# ProPrj_Maggy_4_1_2025-02-07.net
KiCad netlist of a schematic drawn in EasyEDA Pro
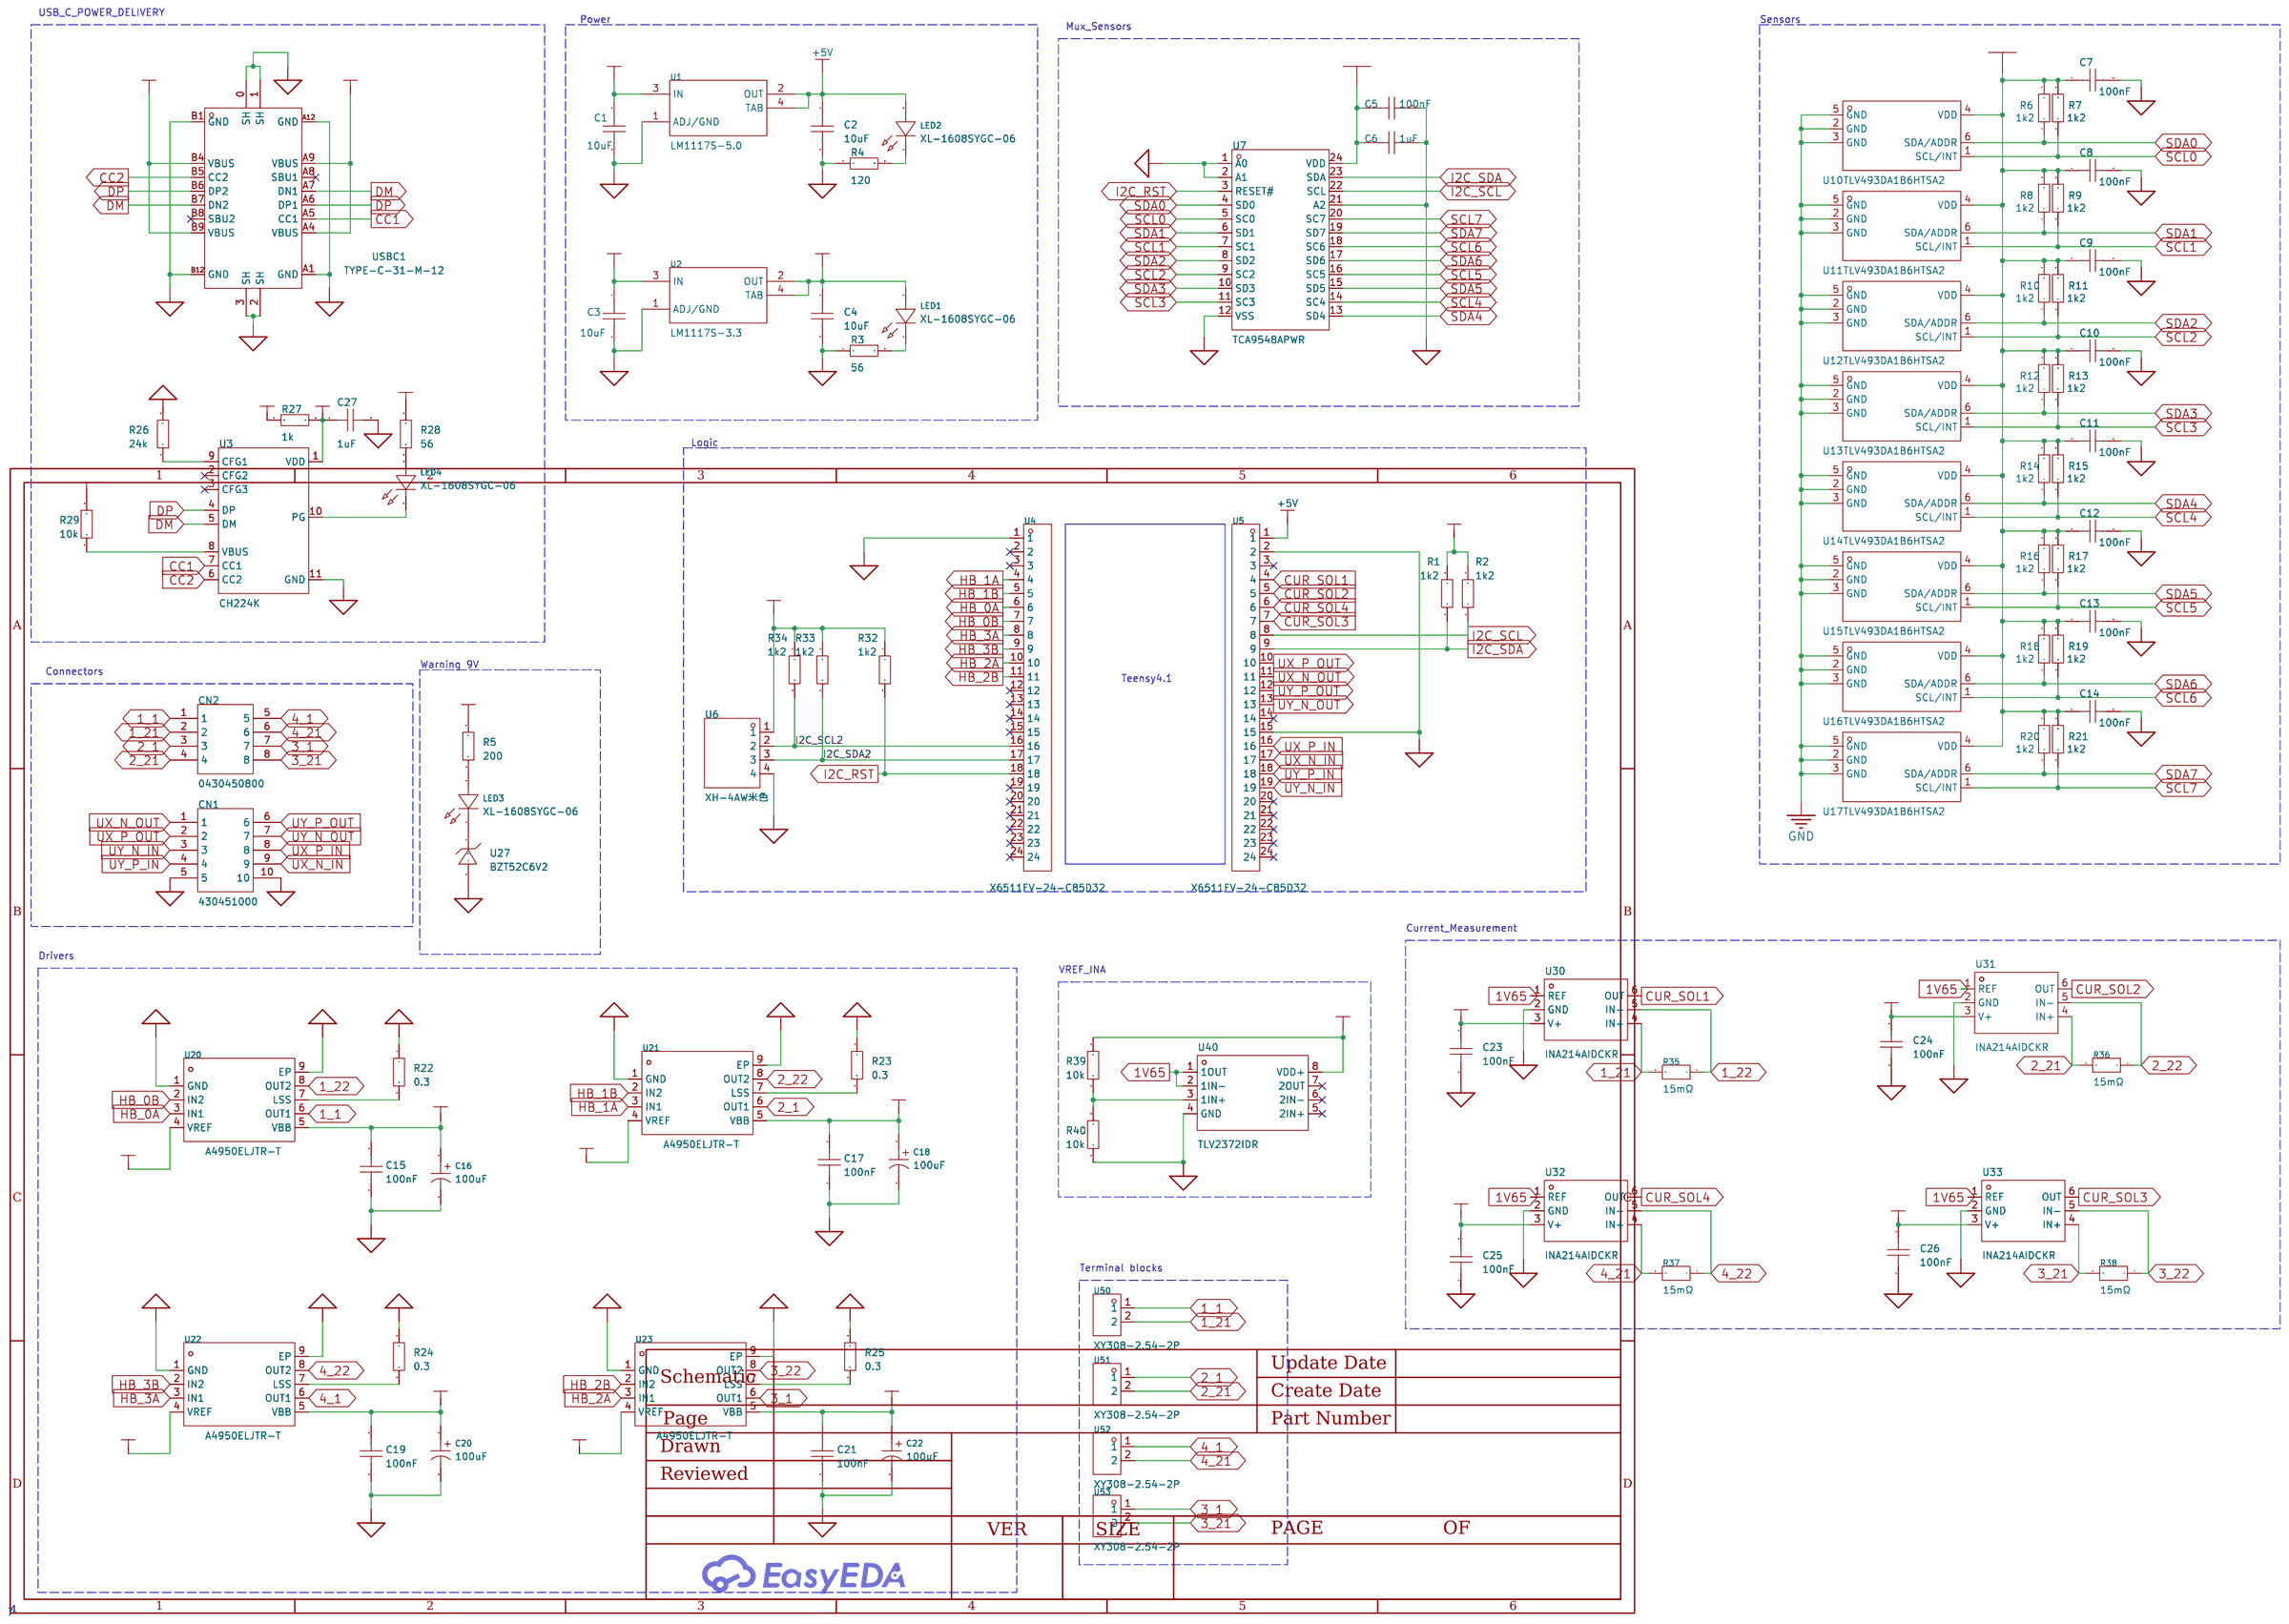
[diagram p0: schematic sheet]

(export (version "E")
  (design (tool "Eeschema 10.0.6"))
  (components
    (comp (ref "C1")
      (value "10uF")
      (footprint "easyedapro:C0805")
      (libsource (lib "easyedapro") (part "CAP"))
    )
    (comp (ref "C2")
      (value "10uF")
      (footprint "easyedapro:C0805")
      (libsource (lib "easyedapro") (part "CAP"))
    )
    (comp (ref "C3")
      (value "10uF")
      (footprint "easyedapro:C0805")
      (libsource (lib "easyedapro") (part "CAP"))
    )
    (comp (ref "C4")
      (value "10uF")
      (footprint "easyedapro:C0805")
      (libsource (lib "easyedapro") (part "CAP"))
    )
    (comp (ref "C5")
      (value "100nF")
      (footprint "easyedapro:C0805")
      (libsource (lib "easyedapro") (part "CAP"))
    )
    (comp (ref "C6") (value "1uF") (footprint "easyedapro:C0805") (libsource (lib "easyedapro") (part "CAP")))
    (comp (ref "C7")
      (value "100nF")
      (footprint "easyedapro:C0805")
      (libsource (lib "easyedapro") (part "CAP"))
    )
    (comp (ref "C8")
      (value "100nF")
      (footprint "easyedapro:C0805")
      (libsource (lib "easyedapro") (part "CAP"))
    )
    (comp (ref "C9")
      (value "100nF")
      (footprint "easyedapro:C0805")
      (libsource (lib "easyedapro") (part "CAP"))
    )
    (comp (ref "C10")
      (value "100nF")
      (footprint "easyedapro:C0805")
      (libsource (lib "easyedapro") (part "CAP"))
    )
    (comp (ref "C11")
      (value "100nF")
      (footprint "easyedapro:C0805")
      (libsource (lib "easyedapro") (part "CAP"))
    )
    (comp (ref "C12")
      (value "100nF")
      (footprint "easyedapro:C0805")
      (libsource (lib "easyedapro") (part "CAP"))
    )
    (comp (ref "C13")
      (value "100nF")
      (footprint "easyedapro:C0805")
      (libsource (lib "easyedapro") (part "CAP"))
    )
    (comp (ref "C14")
      (value "100nF")
      (footprint "easyedapro:C0805")
      (libsource (lib "easyedapro") (part "CAP"))
    )
    (comp (ref "C15")
      (value "100nF")
      (footprint "easyedapro:C0805")
      (libsource (lib "easyedapro") (part "CAP"))
    )
    (comp (ref "C16")
      (value "100uF")
      (footprint "easyedapro:CAP-SMD_BD6.3-L6.6-W6.6-LS7.2-FD")
      (fields (field (name "Manufacturer Part") "RST100UF35V009") (field (name "Manufacturer") "KNSCHA(科尼盛)"))
      (libsource (lib "easyedapro") (part "RST100UF35V009"))
    )
    (comp (ref "C17")
      (value "100nF")
      (footprint "easyedapro:C0805")
      (libsource (lib "easyedapro") (part "CAP"))
    )
    (comp (ref "C18")
      (value "100uF")
      (footprint "easyedapro:CAP-SMD_BD6.3-L6.6-W6.6-LS7.2-FD")
      (fields (field (name "Manufacturer Part") "RST100UF35V009") (field (name "Manufacturer") "KNSCHA(科尼盛)"))
      (libsource (lib "easyedapro") (part "RST100UF35V009"))
    )
    (comp (ref "C19")
      (value "100nF")
      (footprint "easyedapro:C0805")
      (libsource (lib "easyedapro") (part "CAP"))
    )
    (comp (ref "C20")
      (value "100uF")
      (footprint "easyedapro:CAP-SMD_BD6.3-L6.6-W6.6-LS7.2-FD")
      (fields (field (name "Manufacturer Part") "RST100UF35V009") (field (name "Manufacturer") "KNSCHA(科尼盛)"))
      (libsource (lib "easyedapro") (part "RST100UF35V009"))
    )
    (comp (ref "C21")
      (value "100nF")
      (footprint "easyedapro:C0805")
      (libsource (lib "easyedapro") (part "CAP"))
    )
    (comp (ref "C22")
      (value "100uF")
      (footprint "easyedapro:CAP-SMD_BD6.3-L6.6-W6.6-LS7.2-FD")
      (fields (field (name "Manufacturer Part") "RST100UF35V009") (field (name "Manufacturer") "KNSCHA(科尼盛)"))
      (libsource (lib "easyedapro") (part "RST100UF35V009"))
    )
    (comp (ref "C23")
      (value "100nF")
      (footprint "easyedapro:C0805")
      (libsource (lib "easyedapro") (part "CAP"))
    )
    (comp (ref "C24")
      (value "100nF")
      (footprint "easyedapro:C0805")
      (libsource (lib "easyedapro") (part "CAP"))
    )
    (comp (ref "C25")
      (value "100nF")
      (footprint "easyedapro:C0805")
      (libsource (lib "easyedapro") (part "CAP"))
    )
    (comp (ref "C26")
      (value "100nF")
      (footprint "easyedapro:C0805")
      (libsource (lib "easyedapro") (part "CAP"))
    )
    (comp (ref "C27")
      (value "1uF")
      (footprint "easyedapro:C0805")
      (libsource (lib "easyedapro") (part "CAP"))
    )
    (comp (ref "CN1")
      (value "430451000")
      (footprint "easyedapro:CONN-TH_43045-1000")
      (fields (field (name "Manufacturer") "MOLEX"))
      (libsource (lib "easyedapro") (part "0430451000"))
    )
    (comp (ref "CN2")
      (value "0430450800")
      (footprint "easyedapro:CONN-TH_0430450800")
      (fields (field (name "Manufacturer") "MOLEX"))
      (libsource (lib "easyedapro") (part "0430450800"))
    )
    (comp (ref "LED1")
      (value "XL-1608SYGC-06")
      (footprint "easyedapro:LED0603-RD_GREEN")
      (fields (field (name "Manufacturer") "XINGLIGHT(成兴光)"))
      (libsource (lib "easyedapro") (part "XL-1608SYGC-06"))
    )
    (comp (ref "LED2")
      (value "XL-1608SYGC-06")
      (footprint "easyedapro:LED0603-RD_RED")
      (fields (field (name "Manufacturer") "XINGLIGHT(成兴光)"))
      (libsource (lib "easyedapro") (part "XL-1608SURC-06"))
    )
    (comp (ref "LED3")
      (value "XL-1608SYGC-06")
      (footprint "easyedapro:LED0603-RD_GREEN")
      (fields (field (name "Manufacturer") "XINGLIGHT(成兴光)"))
      (libsource (lib "easyedapro") (part "XL-1608SYGC-06"))
    )
    (comp (ref "LED4")
      (value "XL-1608SYGC-06")
      (footprint "easyedapro:LED0603-RD_GREEN")
      (fields (field (name "Manufacturer") "XINGLIGHT(成兴光)"))
      (libsource (lib "easyedapro") (part "XL-1608SYGC-06"))
    )
    (comp (ref "R1") (value "1k2") (footprint "easyedapro:R0805") (libsource (lib "easyedapro") (part "Res")))
    (comp (ref "R2") (value "1k2") (footprint "easyedapro:R0805") (libsource (lib "easyedapro") (part "Res")))
    (comp (ref "R3") (value "56") (footprint "easyedapro:R0805") (libsource (lib "easyedapro") (part "Res")))
    (comp (ref "R4") (value "120") (footprint "easyedapro:R0805") (libsource (lib "easyedapro") (part "Res")))
    (comp (ref "R5") (value "200") (footprint "easyedapro:R0805") (libsource (lib "easyedapro") (part "Res")))
    (comp (ref "R6") (value "1k2") (libsource (lib "easyedapro") (part "Res")))
    (comp (ref "R7") (value "1k2") (libsource (lib "easyedapro") (part "Res")))
    (comp (ref "R8") (value "1k2") (libsource (lib "easyedapro") (part "Res")))
    (comp (ref "R9") (value "1k2") (libsource (lib "easyedapro") (part "Res")))
    (comp (ref "R10") (value "1k2") (libsource (lib "easyedapro") (part "Res")))
    (comp (ref "R11") (value "1k2") (libsource (lib "easyedapro") (part "Res")))
    (comp (ref "R12") (value "1k2") (libsource (lib "easyedapro") (part "Res")))
    (comp (ref "R13") (value "1k2") (libsource (lib "easyedapro") (part "Res")))
    (comp (ref "R14") (value "1k2") (libsource (lib "easyedapro") (part "Res")))
    (comp (ref "R15") (value "1k2") (libsource (lib "easyedapro") (part "Res")))
    (comp (ref "R16") (value "1k2") (libsource (lib "easyedapro") (part "Res")))
    (comp (ref "R17") (value "1k2") (libsource (lib "easyedapro") (part "Res")))
    (comp (ref "R18") (value "1k2") (libsource (lib "easyedapro") (part "Res")))
    (comp (ref "R19") (value "1k2") (libsource (lib "easyedapro") (part "Res")))
    (comp (ref "R20") (value "1k2") (libsource (lib "easyedapro") (part "Res")))
    (comp (ref "R21") (value "1k2") (libsource (lib "easyedapro") (part "Res")))
    (comp (ref "R22")
      (value "0.3")
      (footprint "easyedapro:R0805")
      (libsource (lib "easyedapro") (part "Res"))
    )
    (comp (ref "R23")
      (value "0.3")
      (footprint "easyedapro:R0805")
      (libsource (lib "easyedapro") (part "Res"))
    )
    (comp (ref "R24")
      (value "0.3")
      (footprint "easyedapro:R0805")
      (libsource (lib "easyedapro") (part "Res"))
    )
    (comp (ref "R25")
      (value "0.3")
      (footprint "easyedapro:R0805")
      (libsource (lib "easyedapro") (part "Res"))
    )
    (comp (ref "R26") (value "24k") (libsource (lib "easyedapro") (part "Res")))
    (comp (ref "R27") (value "1k") (libsource (lib "easyedapro") (part "Res")))
    (comp (ref "R28") (value "56") (footprint "easyedapro:R0805") (libsource (lib "easyedapro") (part "Res")))
    (comp (ref "R29") (value "10k") (libsource (lib "easyedapro") (part "Res")))
    (comp (ref "R32")
      (value "1k2")
      (footprint "easyedapro:R0805")
      (libsource (lib "easyedapro") (part "Res"))
    )
    (comp (ref "R33")
      (value "1k2")
      (footprint "easyedapro:R0805")
      (libsource (lib "easyedapro") (part "Res"))
    )
    (comp (ref "R34")
      (value "1k2")
      (footprint "easyedapro:R0805")
      (libsource (lib "easyedapro") (part "Res"))
    )
    (comp (ref "R35")
      (value "15mΩ")
      (footprint "easyedapro:R1206")
      (fields
        (field (name "Manufacturer Part") "1206W3F100MT5E")
        (field (name "Manufacturer") "UNI-ROYAL(厚声)")
      )
      (libsource (lib "easyedapro") (part "1206W3F100MT5E"))
    )
    (comp (ref "R36")
      (value "15mΩ")
      (footprint "easyedapro:R1206")
      (fields
        (field (name "Manufacturer Part") "1206W3F100MT5E")
        (field (name "Manufacturer") "UNI-ROYAL(厚声)")
      )
      (libsource (lib "easyedapro") (part "1206W3F100MT5E"))
    )
    (comp (ref "R37")
      (value "15mΩ")
      (footprint "easyedapro:R1206")
      (fields
        (field (name "Manufacturer Part") "1206W3F100MT5E")
        (field (name "Manufacturer") "UNI-ROYAL(厚声)")
      )
      (libsource (lib "easyedapro") (part "1206W3F100MT5E"))
    )
    (comp (ref "R38")
      (value "15mΩ")
      (footprint "easyedapro:R1206")
      (fields
        (field (name "Manufacturer Part") "1206W3F100MT5E")
        (field (name "Manufacturer") "UNI-ROYAL(厚声)")
      )
      (libsource (lib "easyedapro") (part "1206W3F100MT5E"))
    )
    (comp (ref "R39") (value "10k") (libsource (lib "easyedapro") (part "Res")))
    (comp (ref "R40") (value "10k") (libsource (lib "easyedapro") (part "Res")))
    (comp (ref "U1")
      (value "LM1117S-5.0")
      (footprint "easyedapro:SOT-223-3_L6.5-W3.4-P2.30-LS7.0-BR")
      (fields (field (name "Manufacturer") "HTC"))
      (libsource (lib "easyedapro") (part "LM1117S-5.0"))
    )
    (comp (ref "U2")
      (value "LM1117S-3.3")
      (footprint "easyedapro:SOT-223-3_L6.5-W3.4-P2.30-LS7.0-BR")
      (fields (field (name "Manufacturer") "HTC"))
      (libsource (lib "easyedapro") (part "LM1117S-3.3"))
    )
    (comp (ref "U3")
      (value "CH224K")
      (footprint "easyedapro:ESSOP-10_L4.9-W3.9-P1.0-LS6.0-TL-EP")
      (description "Applications Function:USB充电芯片")
      (fields (field (name "Manufacturer") "WCH(南京沁恒)"))
      (libsource (lib "easyedapro") (part "CH224K"))
    )
    (comp (ref "U4")
      (value "X6511FV-24-C85D32")
      (footprint "easyedapro:HDR-TH_24P-P2.54-V-F")
      (fields (field (name "Manufacturer") "XKB Connectivity(中国星坤)"))
      (libsource (lib "easyedapro") (part "X6511FV-24-C85D32"))
    )
    (comp (ref "U5")
      (value "X6511FV-24-C85D32")
      (footprint "easyedapro:HDR-TH_24P-P2.54-V-F")
      (fields (field (name "Manufacturer") "XKB Connectivity(中国星坤)"))
      (libsource (lib "easyedapro") (part "X6511FV-24-C85D32"))
    )
    (comp (ref "U6")
      (value "XH-4AW米色")
      (fields (field (name "Manufacturer") "BOOMELE(博穆精密)"))
      (libsource (lib "easyedapro") (part "S4B-PH-KL(LF)(SN)"))
    )
    (comp (ref "U7")
      (value "TCA9548APWR")
      (fields (field (name "Manufacturer") "TI(德州仪器)"))
      (libsource (lib "easyedapro") (part "PCA9548APW"))
    )
    (comp (ref "U10")
      (value "TLV493DA1B6HTSA2")
      (fields (field (name "Manufacturer") "Infineon(英飞凌)"))
      (libsource (lib "easyedapro") (part "TLV493DA1B6HTSA2"))
    )
    (comp (ref "U11")
      (value "TLV493DA1B6HTSA2")
      (fields (field (name "Manufacturer") "Infineon(英飞凌)"))
      (libsource (lib "easyedapro") (part "TLV493DA1B6HTSA2"))
    )
    (comp (ref "U12")
      (value "TLV493DA1B6HTSA2")
      (fields (field (name "Manufacturer") "Infineon(英飞凌)"))
      (libsource (lib "easyedapro") (part "TLV493DA1B6HTSA2"))
    )
    (comp (ref "U13")
      (value "TLV493DA1B6HTSA2")
      (fields (field (name "Manufacturer") "Infineon(英飞凌)"))
      (libsource (lib "easyedapro") (part "TLV493DA1B6HTSA2"))
    )
    (comp (ref "U14")
      (value "TLV493DA1B6HTSA2")
      (fields (field (name "Manufacturer") "Infineon(英飞凌)"))
      (libsource (lib "easyedapro") (part "TLV493DA1B6HTSA2"))
    )
    (comp (ref "U15")
      (value "TLV493DA1B6HTSA2")
      (fields (field (name "Manufacturer") "Infineon(英飞凌)"))
      (libsource (lib "easyedapro") (part "TLV493DA1B6HTSA2"))
    )
    (comp (ref "U16")
      (value "TLV493DA1B6HTSA2")
      (fields (field (name "Manufacturer") "Infineon(英飞凌)"))
      (libsource (lib "easyedapro") (part "TLV493DA1B6HTSA2"))
    )
    (comp (ref "U17")
      (value "TLV493DA1B6HTSA2")
      (fields (field (name "Manufacturer") "Infineon(英飞凌)"))
      (libsource (lib "easyedapro") (part "TLV493DA1B6HTSA2"))
    )
    (comp (ref "U20")
      (value "A4950ELJTR-T")
      (footprint "easyedapro:SOIC-8_L4.9-W3.9-P1.27-LS6.0-BL-EP")
      (fields (field (name "Manufacturer") "ALLEGRO(美国埃戈罗)"))
      (libsource (lib "easyedapro") (part "A4950ELJTR-T"))
    )
    (comp (ref "U21")
      (value "A4950ELJTR-T")
      (footprint "easyedapro:SOIC-8_L4.9-W3.9-P1.27-LS6.0-BL-EP")
      (fields (field (name "Manufacturer") "ALLEGRO(美国埃戈罗)"))
      (libsource (lib "easyedapro") (part "A4950ELJTR-T"))
    )
    (comp (ref "U22")
      (value "A4950ELJTR-T")
      (footprint "easyedapro:SOIC-8_L4.9-W3.9-P1.27-LS6.0-BL-EP")
      (fields (field (name "Manufacturer") "ALLEGRO(美国埃戈罗)"))
      (libsource (lib "easyedapro") (part "A4950ELJTR-T"))
    )
    (comp (ref "U23")
      (value "A4950ELJTR-T")
      (footprint "easyedapro:SOIC-8_L4.9-W3.9-P1.27-LS6.0-BL-EP")
      (fields (field (name "Manufacturer") "ALLEGRO(美国埃戈罗)"))
      (libsource (lib "easyedapro") (part "A4950ELJTR-T"))
    )
    (comp (ref "U27")
      (value "BZT52C6V2")
      (footprint "easyedapro:SOD-123_L2.7-W1.6-LS3.7-RD")
      (fields (field (name "Manufacturer") "CJ(江苏长电/长晶)"))
      (libsource (lib "easyedapro") (part "BZT52C6V2_C2910064"))
    )
    (comp (ref "U30")
      (value "INA214AIDCKR")
      (footprint "easyedapro:TSSOP-6_L2.0-W1.3-P0.65-LS2.0-BR")
      (fields (field (name "Manufacturer") "TI(德州仪器)"))
      (libsource (lib "easyedapro") (part "INA213AIDCKR"))
    )
    (comp (ref "U31")
      (value "INA214AIDCKR")
      (footprint "easyedapro:TSSOP-6_L2.0-W1.3-P0.65-LS2.0-BR")
      (fields (field (name "Manufacturer") "TI(德州仪器)"))
      (libsource (lib "easyedapro") (part "INA213AIDCKR"))
    )
    (comp (ref "U32")
      (value "INA214AIDCKR")
      (footprint "easyedapro:TSSOP-6_L2.0-W1.3-P0.65-LS2.0-BR")
      (fields (field (name "Manufacturer") "TI(德州仪器)"))
      (libsource (lib "easyedapro") (part "INA213AIDCKR"))
    )
    (comp (ref "U33")
      (value "INA214AIDCKR")
      (footprint "easyedapro:TSSOP-6_L2.0-W1.3-P0.65-LS2.0-BR")
      (fields (field (name "Manufacturer") "TI(德州仪器)"))
      (libsource (lib "easyedapro") (part "INA213AIDCKR"))
    )
    (comp (ref "U40")
      (value "TLV2372IDR")
      (footprint "easyedapro:SOIC-8_L4.9-W3.9-P1.27-LS6.0-BL")
      (fields (field (name "Manufacturer") "TI(德州仪器)"))
      (libsource (lib "easyedapro") (part "TLV2372IDR"))
    )
    (comp (ref "U50")
      (value "XY308-2.54-2P")
      (footprint "easyedapro:CONN-TH_XY308-2.54-2P")
      (fields (field (name "Manufacturer") "XINLAIYA(新莱亚)"))
      (libsource (lib "easyedapro") (part "XY308-2.54-2P"))
    )
    (comp (ref "U51")
      (value "XY308-2.54-2P")
      (footprint "easyedapro:CONN-TH_XY308-2.54-2P")
      (fields (field (name "Manufacturer") "XINLAIYA(新莱亚)"))
      (libsource (lib "easyedapro") (part "XY308-2.54-2P"))
    )
    (comp (ref "U52")
      (value "XY308-2.54-2P")
      (footprint "easyedapro:CONN-TH_XY308-2.54-2P")
      (fields (field (name "Manufacturer") "XINLAIYA(新莱亚)"))
      (libsource (lib "easyedapro") (part "XY308-2.54-2P"))
    )
    (comp (ref "U53")
      (value "XY308-2.54-2P")
      (footprint "easyedapro:CONN-TH_XY308-2.54-2P")
      (fields (field (name "Manufacturer") "XINLAIYA(新莱亚)"))
      (libsource (lib "easyedapro") (part "XY308-2.54-2P"))
    )
    (comp (ref "USBC1")
      (value "TYPE-C-31-M-12")
      (footprint "easyedapro:USB-C_SMD-TYPE-C-31-M-12")
      (fields (field (name "Manufacturer") "韩国韩荣"))
      (libsource (lib "easyedapro") (part "TYPE-C-31-M-12"))
    )
  )
  (nets
    (net (code "1") (name "+5V") (class "Default")
      (node (ref "C2") (pin "1") (pinfunction "1_1") (pintype "input"))
      (node (ref "LED2") (pin "2") (pinfunction "A_2") (pintype "unspecified"))
      (node (ref "U1") (pin "2") (pinfunction "OUT_2") (pintype "input"))
      (node (ref "U1") (pin "4") (pinfunction "TAB_4") (pintype "input"))
      (node (ref "U5") (pin "1") (pinfunction "1_1") (pintype "input"))
    )
    (net (code "2") (name "/I2C_SCL2") (class "Default")
      (node (ref "R34") (pin "2") (pinfunction "2_2") (pintype "input"))
      (node (ref "U4") (pin "16") (pinfunction "16_16") (pintype "input"))
      (node (ref "U6") (pin "2") (pinfunction "2_2") (pintype "unspecified"))
    )
    (net (code "3") (name "/I2C_SDA2") (class "Default")
      (node (ref "R33") (pin "2") (pinfunction "2_2") (pintype "input"))
      (node (ref "U4") (pin "17") (pinfunction "17_17") (pintype "input"))
      (node (ref "U6") (pin "3") (pinfunction "3_3") (pintype "unspecified"))
    )
    (net (code "4") (name "1V65") (class "Default")
      (node (ref "U30") (pin "1") (pinfunction "REF_1") (pintype "unspecified"))
      (node (ref "U31") (pin "1") (pinfunction "REF_1") (pintype "unspecified"))
      (node (ref "U32") (pin "1") (pinfunction "REF_1") (pintype "unspecified"))
      (node (ref "U33") (pin "1") (pinfunction "REF_1") (pintype "unspecified"))
      (node (ref "U40") (pin "1") (pinfunction "1OUT_1") (pintype "unspecified"))
      (node (ref "U40") (pin "2") (pinfunction "1IN-_2") (pintype "unspecified"))
    )
    (net (code "5") (name "1_1") (class "Default")
      (node (ref "CN2") (pin "1") (pinfunction "1_1") (pintype "unspecified"))
      (node (ref "U20") (pin "6") (pinfunction "OUT1_6") (pintype "unspecified"))
      (node (ref "U50") (pin "1") (pinfunction "1_1") (pintype "unspecified"))
    )
    (net (code "6") (name "1_21") (class "Default")
      (node (ref "CN2") (pin "2") (pinfunction "2_2") (pintype "unspecified"))
      (node (ref "R35") (pin "2") (pinfunction "2_2") (pintype "input"))
      (node (ref "U30") (pin "4") (pinfunction "IN+_4") (pintype "unspecified"))
      (node (ref "U50") (pin "2") (pinfunction "2_2") (pintype "unspecified"))
    )
    (net (code "7") (name "1_22") (class "Default")
      (node (ref "R35") (pin "1") (pinfunction "1_1") (pintype "input"))
      (node (ref "U20") (pin "8") (pinfunction "OUT2_8") (pintype "unspecified"))
      (node (ref "U30") (pin "5") (pinfunction "IN-_5") (pintype "unspecified"))
    )
    (net (code "8") (name "2_1") (class "Default")
      (node (ref "CN2") (pin "3") (pinfunction "3_3") (pintype "unspecified"))
      (node (ref "U21") (pin "6") (pinfunction "OUT1_6") (pintype "unspecified"))
      (node (ref "U51") (pin "1") (pinfunction "1_1") (pintype "unspecified"))
    )
    (net (code "9") (name "2_21") (class "Default")
      (node (ref "CN2") (pin "4") (pinfunction "4_4") (pintype "unspecified"))
      (node (ref "R36") (pin "2") (pinfunction "2_2") (pintype "input"))
      (node (ref "U31") (pin "4") (pinfunction "IN+_4") (pintype "unspecified"))
      (node (ref "U51") (pin "2") (pinfunction "2_2") (pintype "unspecified"))
    )
    (net (code "10") (name "2_22") (class "Default")
      (node (ref "R36") (pin "1") (pinfunction "1_1") (pintype "input"))
      (node (ref "U21") (pin "8") (pinfunction "OUT2_8") (pintype "unspecified"))
      (node (ref "U31") (pin "5") (pinfunction "IN-_5") (pintype "unspecified"))
    )
    (net (code "11") (name "3V3") (class "Default")
      (node (ref "C10") (pin "1") (pinfunction "1_1") (pintype "input"))
      (node (ref "C11") (pin "1") (pinfunction "1_1") (pintype "input"))
      (node (ref "C12") (pin "1") (pinfunction "1_1") (pintype "input"))
      (node (ref "C13") (pin "1") (pinfunction "1_1") (pintype "input"))
      (node (ref "C14") (pin "1") (pinfunction "1_1") (pintype "input"))
      (node (ref "C23") (pin "2") (pinfunction "2_2") (pintype "input"))
      (node (ref "C24") (pin "2") (pinfunction "2_2") (pintype "input"))
      (node (ref "C25") (pin "2") (pinfunction "2_2") (pintype "input"))
      (node (ref "C26") (pin "2") (pinfunction "2_2") (pintype "input"))
      (node (ref "C27") (pin "1") (pinfunction "1_1") (pintype "input"))
      (node (ref "C4") (pin "1") (pinfunction "1_1") (pintype "input"))
      (node (ref "C5") (pin "1") (pinfunction "1_1") (pintype "input"))
      (node (ref "C6") (pin "2") (pinfunction "2_2") (pintype "input"))
      (node (ref "C7") (pin "1") (pinfunction "1_1") (pintype "input"))
      (node (ref "C8") (pin "1") (pinfunction "1_1") (pintype "input"))
      (node (ref "C9") (pin "1") (pinfunction "1_1") (pintype "input"))
      (node (ref "LED1") (pin "2") (pinfunction "A_2") (pintype "input"))
      (node (ref "R1") (pin "2") (pinfunction "2_2") (pintype "input"))
      (node (ref "R10") (pin "2") (pinfunction "2_2") (pintype "input"))
      (node (ref "R11") (pin "2") (pinfunction "2_2") (pintype "input"))
      (node (ref "R12") (pin "2") (pinfunction "2_2") (pintype "input"))
      (node (ref "R13") (pin "2") (pinfunction "2_2") (pintype "input"))
      (node (ref "R14") (pin "2") (pinfunction "2_2") (pintype "input"))
      (node (ref "R15") (pin "2") (pinfunction "2_2") (pintype "input"))
      (node (ref "R16") (pin "2") (pinfunction "2_2") (pintype "input"))
      (node (ref "R17") (pin "2") (pinfunction "2_2") (pintype "input"))
      (node (ref "R18") (pin "2") (pinfunction "2_2") (pintype "input"))
      (node (ref "R19") (pin "2") (pinfunction "2_2") (pintype "input"))
      (node (ref "R2") (pin "2") (pinfunction "2_2") (pintype "input"))
      (node (ref "R20") (pin "2") (pinfunction "2_2") (pintype "input"))
      (node (ref "R21") (pin "2") (pinfunction "2_2") (pintype "input"))
      (node (ref "R27") (pin "1") (pinfunction "1_1") (pintype "input"))
      (node (ref "R28") (pin "2") (pinfunction "2_2") (pintype "input"))
      (node (ref "R32") (pin "1") (pinfunction "1_1") (pintype "input"))
      (node (ref "R33") (pin "1") (pinfunction "1_1") (pintype "input"))
      (node (ref "R34") (pin "1") (pinfunction "1_1") (pintype "input"))
      (node (ref "R39") (pin "2") (pinfunction "2_2") (pintype "input"))
      (node (ref "R6") (pin "2") (pinfunction "2_2") (pintype "input"))
      (node (ref "R7") (pin "2") (pinfunction "2_2") (pintype "input"))
      (node (ref "R8") (pin "2") (pinfunction "2_2") (pintype "input"))
      (node (ref "R9") (pin "2") (pinfunction "2_2") (pintype "input"))
      (node (ref "U10") (pin "4") (pinfunction "VDD_4") (pintype "input"))
      (node (ref "U11") (pin "4") (pinfunction "VDD_4") (pintype "input"))
      (node (ref "U12") (pin "4") (pinfunction "VDD_4") (pintype "input"))
      (node (ref "U13") (pin "4") (pinfunction "VDD_4") (pintype "input"))
      (node (ref "U14") (pin "4") (pinfunction "VDD_4") (pintype "input"))
      (node (ref "U15") (pin "4") (pinfunction "VDD_4") (pintype "input"))
      (node (ref "U16") (pin "4") (pinfunction "VDD_4") (pintype "input"))
      (node (ref "U17") (pin "4") (pinfunction "VDD_4") (pintype "input"))
      (node (ref "U2") (pin "2") (pinfunction "OUT_2") (pintype "input"))
      (node (ref "U2") (pin "4") (pinfunction "TAB_4") (pintype "input"))
      (node (ref "U20") (pin "4") (pinfunction "VREF_4") (pintype "unspecified"))
      (node (ref "U21") (pin "4") (pinfunction "VREF_4") (pintype "unspecified"))
      (node (ref "U22") (pin "4") (pinfunction "VREF_4") (pintype "unspecified"))
      (node (ref "U23") (pin "4") (pinfunction "VREF_4") (pintype "unspecified"))
      (node (ref "U3") (pin "1") (pinfunction "VDD_1") (pintype "unspecified"))
      (node (ref "U30") (pin "3") (pinfunction "V+_3") (pintype "unspecified"))
      (node (ref "U31") (pin "3") (pinfunction "V+_3") (pintype "unspecified"))
      (node (ref "U32") (pin "3") (pinfunction "V+_3") (pintype "unspecified"))
      (node (ref "U33") (pin "3") (pinfunction "V+_3") (pintype "unspecified"))
      (node (ref "U40") (pin "8") (pinfunction "VDD+_8") (pintype "unspecified"))
      (node (ref "U6") (pin "1") (pinfunction "1_1") (pintype "unspecified"))
      (node (ref "U7") (pin "24") (pinfunction "VDD_24") (pintype "unspecified"))
    )
    (net (code "12") (name "3_1") (class "Default")
      (node (ref "CN2") (pin "7") (pinfunction "7_7") (pintype "unspecified"))
      (node (ref "U23") (pin "6") (pinfunction "OUT1_6") (pintype "unspecified"))
      (node (ref "U53") (pin "1") (pinfunction "1_1") (pintype "unspecified"))
    )
    (net (code "13") (name "3_21") (class "Default")
      (node (ref "CN2") (pin "8") (pinfunction "8_8") (pintype "unspecified"))
      (node (ref "R38") (pin "2") (pinfunction "2_2") (pintype "input"))
      (node (ref "U33") (pin "4") (pinfunction "IN+_4") (pintype "unspecified"))
      (node (ref "U53") (pin "2") (pinfunction "2_2") (pintype "unspecified"))
    )
    (net (code "14") (name "3_22") (class "Default")
      (node (ref "R38") (pin "1") (pinfunction "1_1") (pintype "input"))
      (node (ref "U23") (pin "8") (pinfunction "OUT2_8") (pintype "unspecified"))
      (node (ref "U33") (pin "5") (pinfunction "IN-_5") (pintype "unspecified"))
    )
    (net (code "15") (name "4_1") (class "Default")
      (node (ref "CN2") (pin "5") (pinfunction "5_5") (pintype "unspecified"))
      (node (ref "U22") (pin "6") (pinfunction "OUT1_6") (pintype "unspecified"))
      (node (ref "U52") (pin "1") (pinfunction "1_1") (pintype "unspecified"))
    )
    (net (code "16") (name "4_21") (class "Default")
      (node (ref "CN2") (pin "6") (pinfunction "6_6") (pintype "unspecified"))
      (node (ref "R37") (pin "2") (pinfunction "2_2") (pintype "input"))
      (node (ref "U32") (pin "4") (pinfunction "IN+_4") (pintype "unspecified"))
      (node (ref "U52") (pin "2") (pinfunction "2_2") (pintype "unspecified"))
    )
    (net (code "17") (name "4_22") (class "Default")
      (node (ref "R37") (pin "1") (pinfunction "1_1") (pintype "input"))
      (node (ref "U22") (pin "8") (pinfunction "OUT2_8") (pintype "unspecified"))
      (node (ref "U32") (pin "5") (pinfunction "IN-_5") (pintype "unspecified"))
    )
    (net (code "18") (name "CC1") (class "Default")
      (node (ref "U3") (pin "7") (pinfunction "CC1_7") (pintype "unspecified"))
      (node (ref "USBC1") (pin "A5") (pinfunction "CC1_A5") (pintype "unspecified"))
    )
    (net (code "19") (name "CC2") (class "Default")
      (node (ref "U3") (pin "6") (pinfunction "CC2_6") (pintype "unspecified"))
      (node (ref "USBC1") (pin "B5") (pinfunction "CC2_B5") (pintype "unspecified"))
    )
    (net (code "20") (name "CUR_SOL1") (class "Default")
      (node (ref "U30") (pin "6") (pinfunction "OUT_6") (pintype "unspecified"))
      (node (ref "U5") (pin "4") (pinfunction "4_4") (pintype "input"))
    )
    (net (code "21") (name "CUR_SOL2") (class "Default")
      (node (ref "U31") (pin "6") (pinfunction "OUT_6") (pintype "unspecified"))
      (node (ref "U5") (pin "5") (pinfunction "5_5") (pintype "input"))
    )
    (net (code "22") (name "CUR_SOL3") (class "Default")
      (node (ref "U33") (pin "6") (pinfunction "OUT_6") (pintype "unspecified"))
      (node (ref "U5") (pin "7") (pinfunction "7_7") (pintype "input"))
    )
    (net (code "23") (name "CUR_SOL4") (class "Default")
      (node (ref "U32") (pin "6") (pinfunction "OUT_6") (pintype "unspecified"))
      (node (ref "U5") (pin "6") (pinfunction "6_6") (pintype "input"))
    )
    (net (code "24") (name "DM") (class "Default")
      (node (ref "U3") (pin "5") (pinfunction "DM_5") (pintype "unspecified"))
      (node (ref "USBC1") (pin "A7") (pinfunction "DN1_A7") (pintype "unspecified"))
      (node (ref "USBC1") (pin "B7") (pinfunction "DN2_B7") (pintype "unspecified"))
    )
    (net (code "25") (name "DP") (class "Default")
      (node (ref "U3") (pin "4") (pinfunction "DP_4") (pintype "unspecified"))
      (node (ref "USBC1") (pin "A6") (pinfunction "DP1_A6") (pintype "unspecified"))
      (node (ref "USBC1") (pin "B6") (pinfunction "DP2_B6") (pintype "unspecified"))
    )
    (net (code "26") (name "GND") (class "Default")
      (node (ref "C1") (pin "2") (pinfunction "2_2") (pintype "input"))
      (node (ref "C10") (pin "2") (pinfunction "2_2") (pintype "input"))
      (node (ref "C11") (pin "2") (pinfunction "2_2") (pintype "input"))
      (node (ref "C12") (pin "2") (pinfunction "2_2") (pintype "input"))
      (node (ref "C13") (pin "2") (pinfunction "2_2") (pintype "input"))
      (node (ref "C14") (pin "2") (pinfunction "2_2") (pintype "input"))
      (node (ref "C15") (pin "2") (pinfunction "2_2") (pintype "input"))
      (node (ref "C16") (pin "2") (pinfunction "2_2") (pintype "input"))
      (node (ref "C17") (pin "2") (pinfunction "2_2") (pintype "input"))
      (node (ref "C18") (pin "2") (pinfunction "2_2") (pintype "input"))
      (node (ref "C19") (pin "2") (pinfunction "2_2") (pintype "input"))
      (node (ref "C2") (pin "2") (pinfunction "2_2") (pintype "input"))
      (node (ref "C20") (pin "2") (pinfunction "2_2") (pintype "input"))
      (node (ref "C21") (pin "2") (pinfunction "2_2") (pintype "input"))
      (node (ref "C22") (pin "2") (pinfunction "2_2") (pintype "input"))
      (node (ref "C23") (pin "1") (pinfunction "1_1") (pintype "input"))
      (node (ref "C24") (pin "1") (pinfunction "1_1") (pintype "input"))
      (node (ref "C25") (pin "1") (pinfunction "1_1") (pintype "input"))
      (node (ref "C26") (pin "1") (pinfunction "1_1") (pintype "input"))
      (node (ref "C27") (pin "2") (pinfunction "2_2") (pintype "input"))
      (node (ref "C3") (pin "2") (pinfunction "2_2") (pintype "input"))
      (node (ref "C4") (pin "2") (pinfunction "2_2") (pintype "input"))
      (node (ref "C5") (pin "2") (pinfunction "2_2") (pintype "input"))
      (node (ref "C6") (pin "1") (pinfunction "1_1") (pintype "input"))
      (node (ref "C7") (pin "2") (pinfunction "2_2") (pintype "input"))
      (node (ref "C8") (pin "2") (pinfunction "2_2") (pintype "input"))
      (node (ref "C9") (pin "2") (pinfunction "2_2") (pintype "input"))
      (node (ref "CN1") (pin "10") (pinfunction "10_10") (pintype "unspecified"))
      (node (ref "CN1") (pin "5") (pinfunction "5_5") (pintype "unspecified"))
      (node (ref "R22") (pin "1") (pinfunction "1_1") (pintype "input"))
      (node (ref "R23") (pin "1") (pinfunction "1_1") (pintype "input"))
      (node (ref "R24") (pin "1") (pinfunction "1_1") (pintype "input"))
      (node (ref "R25") (pin "1") (pinfunction "1_1") (pintype "input"))
      (node (ref "R26") (pin "2") (pinfunction "2_2") (pintype "input"))
      (node (ref "R3") (pin "1") (pinfunction "1_1") (pintype "input"))
      (node (ref "R4") (pin "1") (pinfunction "1_1") (pintype "input"))
      (node (ref "R40") (pin "1") (pinfunction "1_1") (pintype "input"))
      (node (ref "U1") (pin "1") (pinfunction "ADJ/GND_1") (pintype "input"))
      (node (ref "U10") (pin "2") (pinfunction "GND_2") (pintype "input"))
      (node (ref "U10") (pin "3") (pinfunction "GND_3") (pintype "input"))
      (node (ref "U10") (pin "5") (pinfunction "GND_5") (pintype "input"))
      (node (ref "U11") (pin "2") (pinfunction "GND_2") (pintype "input"))
      (node (ref "U11") (pin "3") (pinfunction "GND_3") (pintype "input"))
      (node (ref "U11") (pin "5") (pinfunction "GND_5") (pintype "input"))
      (node (ref "U12") (pin "2") (pinfunction "GND_2") (pintype "input"))
      (node (ref "U12") (pin "3") (pinfunction "GND_3") (pintype "input"))
      (node (ref "U12") (pin "5") (pinfunction "GND_5") (pintype "input"))
      (node (ref "U13") (pin "2") (pinfunction "GND_2") (pintype "input"))
      (node (ref "U13") (pin "3") (pinfunction "GND_3") (pintype "input"))
      (node (ref "U13") (pin "5") (pinfunction "GND_5") (pintype "input"))
      (node (ref "U14") (pin "2") (pinfunction "GND_2") (pintype "input"))
      (node (ref "U14") (pin "3") (pinfunction "GND_3") (pintype "input"))
      (node (ref "U14") (pin "5") (pinfunction "GND_5") (pintype "input"))
      (node (ref "U15") (pin "2") (pinfunction "GND_2") (pintype "input"))
      (node (ref "U15") (pin "3") (pinfunction "GND_3") (pintype "input"))
      (node (ref "U15") (pin "5") (pinfunction "GND_5") (pintype "input"))
      (node (ref "U16") (pin "2") (pinfunction "GND_2") (pintype "input"))
      (node (ref "U16") (pin "3") (pinfunction "GND_3") (pintype "input"))
      (node (ref "U16") (pin "5") (pinfunction "GND_5") (pintype "input"))
      (node (ref "U17") (pin "2") (pinfunction "GND_2") (pintype "input"))
      (node (ref "U17") (pin "3") (pinfunction "GND_3") (pintype "input"))
      (node (ref "U17") (pin "5") (pinfunction "GND_5") (pintype "input"))
      (node (ref "U2") (pin "1") (pinfunction "ADJ/GND_1") (pintype "input"))
      (node (ref "U20") (pin "1") (pinfunction "GND_1") (pintype "unspecified"))
      (node (ref "U20") (pin "9") (pinfunction "EP_9") (pintype "unspecified"))
      (node (ref "U21") (pin "1") (pinfunction "GND_1") (pintype "unspecified"))
      (node (ref "U21") (pin "9") (pinfunction "EP_9") (pintype "unspecified"))
      (node (ref "U22") (pin "1") (pinfunction "GND_1") (pintype "unspecified"))
      (node (ref "U22") (pin "9") (pinfunction "EP_9") (pintype "unspecified"))
      (node (ref "U23") (pin "1") (pinfunction "GND_1") (pintype "unspecified"))
      (node (ref "U23") (pin "9") (pinfunction "EP_9") (pintype "unspecified"))
      (node (ref "U27") (pin "2") (pinfunction "A_2") (pintype "input"))
      (node (ref "U3") (pin "11") (pinfunction "GND_11") (pintype "unspecified"))
      (node (ref "U30") (pin "2") (pinfunction "GND_2") (pintype "unspecified"))
      (node (ref "U31") (pin "2") (pinfunction "GND_2") (pintype "unspecified"))
      (node (ref "U32") (pin "2") (pinfunction "GND_2") (pintype "unspecified"))
      (node (ref "U33") (pin "2") (pinfunction "GND_2") (pintype "unspecified"))
      (node (ref "U4") (pin "1") (pinfunction "1_1") (pintype "input"))
      (node (ref "U40") (pin "4") (pinfunction "GND_4") (pintype "unspecified"))
      (node (ref "U5") (pin "15") (pinfunction "15_15") (pintype "input"))
      (node (ref "U5") (pin "2") (pinfunction "2_2") (pintype "input"))
      (node (ref "U6") (pin "4") (pinfunction "4_4") (pintype "unspecified"))
      (node (ref "U7") (pin "1") (pinfunction "A0_1") (pintype "unspecified"))
      (node (ref "U7") (pin "12") (pinfunction "VSS_12") (pintype "unspecified"))
      (node (ref "U7") (pin "2") (pinfunction "A1_2") (pintype "unspecified"))
      (node (ref "U7") (pin "21") (pinfunction "A2_21") (pintype "unspecified"))
      (node (ref "USBC1") (pin "0") (pinfunction "SH_0") (pintype "unspecified"))
      (node (ref "USBC1") (pin "1") (pinfunction "SH_1") (pintype "unspecified"))
      (node (ref "USBC1") (pin "2") (pinfunction "SH_2") (pintype "unspecified"))
      (node (ref "USBC1") (pin "3") (pinfunction "SH_3") (pintype "unspecified"))
      (node (ref "USBC1") (pin "A1") (pinfunction "GND_A1") (pintype "unspecified"))
      (node (ref "USBC1") (pin "A12") (pinfunction "GND_A12") (pintype "unspecified"))
      (node (ref "USBC1") (pin "B1") (pinfunction "GND_B1") (pintype "unspecified"))
      (node (ref "USBC1") (pin "B12") (pinfunction "GND_B12") (pintype "unspecified"))
    )
    (net (code "27") (name "HB_0A") (class "Default")
      (node (ref "U20") (pin "3") (pinfunction "IN1_3") (pintype "unspecified"))
      (node (ref "U4") (pin "6") (pinfunction "6_6") (pintype "input"))
    )
    (net (code "28") (name "HB_0B") (class "Default")
      (node (ref "U20") (pin "2") (pinfunction "IN2_2") (pintype "unspecified"))
      (node (ref "U4") (pin "7") (pinfunction "7_7") (pintype "input"))
    )
    (net (code "29") (name "HB_1A") (class "Default")
      (node (ref "U21") (pin "3") (pinfunction "IN1_3") (pintype "unspecified"))
      (node (ref "U4") (pin "4") (pinfunction "4_4") (pintype "input"))
    )
    (net (code "30") (name "HB_1B") (class "Default")
      (node (ref "U21") (pin "2") (pinfunction "IN2_2") (pintype "unspecified"))
      (node (ref "U4") (pin "5") (pinfunction "5_5") (pintype "input"))
    )
    (net (code "31") (name "HB_2A") (class "Default")
      (node (ref "U23") (pin "3") (pinfunction "IN1_3") (pintype "unspecified"))
      (node (ref "U4") (pin "10") (pinfunction "10_10") (pintype "input"))
    )
    (net (code "32") (name "HB_2B") (class "Default")
      (node (ref "U23") (pin "2") (pinfunction "IN2_2") (pintype "unspecified"))
      (node (ref "U4") (pin "11") (pinfunction "11_11") (pintype "input"))
    )
    (net (code "33") (name "HB_3A") (class "Default")
      (node (ref "U22") (pin "3") (pinfunction "IN1_3") (pintype "unspecified"))
      (node (ref "U4") (pin "8") (pinfunction "8_8") (pintype "input"))
    )
    (net (code "34") (name "HB_3B") (class "Default")
      (node (ref "U22") (pin "2") (pinfunction "IN2_2") (pintype "unspecified"))
      (node (ref "U4") (pin "9") (pinfunction "9_9") (pintype "input"))
    )
    (net (code "35") (name "I2C_RST") (class "Default")
      (node (ref "R32") (pin "2") (pinfunction "2_2") (pintype "input"))
      (node (ref "U4") (pin "18") (pinfunction "18_18") (pintype "input"))
      (node (ref "U7") (pin "3") (pinfunction "RESET#_3") (pintype "unspecified"))
    )
    (net (code "36") (name "I2C_SCL") (class "Default")
      (node (ref "R2") (pin "1") (pinfunction "1_1") (pintype "input"))
      (node (ref "U5") (pin "8") (pinfunction "8_8") (pintype "input"))
      (node (ref "U7") (pin "22") (pinfunction "SCL_22") (pintype "unspecified"))
    )
    (net (code "37") (name "I2C_SDA") (class "Default")
      (node (ref "R1") (pin "1") (pinfunction "1_1") (pintype "input"))
      (node (ref "U5") (pin "9") (pinfunction "9_9") (pintype "input"))
      (node (ref "U7") (pin "23") (pinfunction "SDA_23") (pintype "unspecified"))
    )
    (net (code "38") (name "Net-(LED1-K)") (class "Default")
      (node (ref "LED1") (pin "1") (pinfunction "K_1") (pintype "input"))
      (node (ref "R3") (pin "2") (pinfunction "2_2") (pintype "input"))
    )
    (net (code "39") (name "Net-(LED2-K)") (class "Default")
      (node (ref "LED2") (pin "1") (pinfunction "K_1") (pintype "unspecified"))
      (node (ref "R4") (pin "2") (pinfunction "2_2") (pintype "input"))
    )
    (net (code "40") (name "Net-(LED3-A)") (class "Default")
      (node (ref "LED3") (pin "2") (pinfunction "A_2") (pintype "input"))
      (node (ref "R5") (pin "1") (pinfunction "1_1") (pintype "input"))
    )
    (net (code "41") (name "Net-(LED3-K)") (class "Default")
      (node (ref "LED3") (pin "1") (pinfunction "K_1") (pintype "input"))
      (node (ref "U27") (pin "1") (pinfunction "C_1") (pintype "input"))
    )
    (net (code "42") (name "Net-(LED4-A)") (class "Default")
      (node (ref "LED4") (pin "2") (pinfunction "A_2") (pintype "input"))
      (node (ref "R28") (pin "1") (pinfunction "1_1") (pintype "input"))
    )
    (net (code "43") (name "Net-(LED4-K)") (class "Default")
      (node (ref "LED4") (pin "1") (pinfunction "K_1") (pintype "input"))
      (node (ref "U3") (pin "10") (pinfunction "PG_10") (pintype "unspecified"))
    )
    (net (code "44") (name "Net-(U3-CFG1)") (class "Default")
      (node (ref "R26") (pin "1") (pinfunction "1_1") (pintype "input"))
      (node (ref "U3") (pin "9") (pinfunction "CFG1_9") (pintype "unspecified"))
    )
    (net (code "45") (name "Net-(U3-VBUS)") (class "Default")
      (node (ref "R29") (pin "1") (pinfunction "1_1") (pintype "input"))
      (node (ref "U3") (pin "8") (pinfunction "VBUS_8") (pintype "unspecified"))
    )
    (net (code "46") (name "Net-(U20-LSS)") (class "Default")
      (node (ref "R22") (pin "2") (pinfunction "2_2") (pintype "input"))
      (node (ref "U20") (pin "7") (pinfunction "LSS_7") (pintype "unspecified"))
    )
    (net (code "47") (name "Net-(U21-LSS)") (class "Default")
      (node (ref "R23") (pin "2") (pinfunction "2_2") (pintype "input"))
      (node (ref "U21") (pin "7") (pinfunction "LSS_7") (pintype "unspecified"))
    )
    (net (code "48") (name "Net-(U22-LSS)") (class "Default")
      (node (ref "R24") (pin "2") (pinfunction "2_2") (pintype "input"))
      (node (ref "U22") (pin "7") (pinfunction "LSS_7") (pintype "unspecified"))
    )
    (net (code "49") (name "Net-(U23-LSS)") (class "Default")
      (node (ref "R25") (pin "2") (pinfunction "2_2") (pintype "input"))
      (node (ref "U23") (pin "7") (pinfunction "LSS_7") (pintype "unspecified"))
    )
    (net (code "50") (name "Net-(U40-1IN+)") (class "Default")
      (node (ref "R39") (pin "1") (pinfunction "1_1") (pintype "input"))
      (node (ref "R40") (pin "2") (pinfunction "2_2") (pintype "input"))
      (node (ref "U40") (pin "3") (pinfunction "1IN+_3") (pintype "unspecified"))
    )
    (net (code "51") (name "SCL0") (class "Default")
      (node (ref "R7") (pin "1") (pinfunction "1_1") (pintype "input"))
      (node (ref "U10") (pin "1") (pinfunction "SCL/INT_1") (pintype "input"))
      (node (ref "U7") (pin "5") (pinfunction "SC0_5") (pintype "unspecified"))
    )
    (net (code "52") (name "SCL1") (class "Default")
      (node (ref "R9") (pin "1") (pinfunction "1_1") (pintype "input"))
      (node (ref "U11") (pin "1") (pinfunction "SCL/INT_1") (pintype "input"))
      (node (ref "U7") (pin "7") (pinfunction "SC1_7") (pintype "unspecified"))
    )
    (net (code "53") (name "SCL2") (class "Default")
      (node (ref "R11") (pin "1") (pinfunction "1_1") (pintype "input"))
      (node (ref "U12") (pin "1") (pinfunction "SCL/INT_1") (pintype "input"))
      (node (ref "U7") (pin "9") (pinfunction "SC2_9") (pintype "unspecified"))
    )
    (net (code "54") (name "SCL3") (class "Default")
      (node (ref "R13") (pin "1") (pinfunction "1_1") (pintype "input"))
      (node (ref "U13") (pin "1") (pinfunction "SCL/INT_1") (pintype "input"))
      (node (ref "U7") (pin "11") (pinfunction "SC3_11") (pintype "unspecified"))
    )
    (net (code "55") (name "SCL4") (class "Default")
      (node (ref "R15") (pin "1") (pinfunction "1_1") (pintype "input"))
      (node (ref "U14") (pin "1") (pinfunction "SCL/INT_1") (pintype "input"))
      (node (ref "U7") (pin "14") (pinfunction "SC4_14") (pintype "unspecified"))
    )
    (net (code "56") (name "SCL5") (class "Default")
      (node (ref "R17") (pin "1") (pinfunction "1_1") (pintype "input"))
      (node (ref "U15") (pin "1") (pinfunction "SCL/INT_1") (pintype "input"))
      (node (ref "U7") (pin "16") (pinfunction "SC5_16") (pintype "unspecified"))
    )
    (net (code "57") (name "SCL6") (class "Default")
      (node (ref "R19") (pin "1") (pinfunction "1_1") (pintype "input"))
      (node (ref "U16") (pin "1") (pinfunction "SCL/INT_1") (pintype "input"))
      (node (ref "U7") (pin "18") (pinfunction "SC6_18") (pintype "unspecified"))
    )
    (net (code "58") (name "SCL7") (class "Default")
      (node (ref "R21") (pin "1") (pinfunction "1_1") (pintype "input"))
      (node (ref "U17") (pin "1") (pinfunction "SCL/INT_1") (pintype "input"))
      (node (ref "U7") (pin "20") (pinfunction "SC7_20") (pintype "unspecified"))
    )
    (net (code "59") (name "SDA0") (class "Default")
      (node (ref "R6") (pin "1") (pinfunction "1_1") (pintype "input"))
      (node (ref "U10") (pin "6") (pinfunction "SDA/ADDR_6") (pintype "input"))
      (node (ref "U7") (pin "4") (pinfunction "SD0_4") (pintype "unspecified"))
    )
    (net (code "60") (name "SDA1") (class "Default")
      (node (ref "R8") (pin "1") (pinfunction "1_1") (pintype "input"))
      (node (ref "U11") (pin "6") (pinfunction "SDA/ADDR_6") (pintype "input"))
      (node (ref "U7") (pin "6") (pinfunction "SD1_6") (pintype "unspecified"))
    )
    (net (code "61") (name "SDA2") (class "Default")
      (node (ref "R10") (pin "1") (pinfunction "1_1") (pintype "input"))
      (node (ref "U12") (pin "6") (pinfunction "SDA/ADDR_6") (pintype "input"))
      (node (ref "U7") (pin "8") (pinfunction "SD2_8") (pintype "unspecified"))
    )
    (net (code "62") (name "SDA3") (class "Default")
      (node (ref "R12") (pin "1") (pinfunction "1_1") (pintype "input"))
      (node (ref "U13") (pin "6") (pinfunction "SDA/ADDR_6") (pintype "input"))
      (node (ref "U7") (pin "10") (pinfunction "SD3_10") (pintype "unspecified"))
    )
    (net (code "63") (name "SDA4") (class "Default")
      (node (ref "R14") (pin "1") (pinfunction "1_1") (pintype "input"))
      (node (ref "U14") (pin "6") (pinfunction "SDA/ADDR_6") (pintype "input"))
      (node (ref "U7") (pin "13") (pinfunction "SD4_13") (pintype "unspecified"))
    )
    (net (code "64") (name "SDA5") (class "Default")
      (node (ref "R16") (pin "1") (pinfunction "1_1") (pintype "input"))
      (node (ref "U15") (pin "6") (pinfunction "SDA/ADDR_6") (pintype "input"))
      (node (ref "U7") (pin "15") (pinfunction "SD5_15") (pintype "unspecified"))
    )
    (net (code "65") (name "SDA6") (class "Default")
      (node (ref "R18") (pin "1") (pinfunction "1_1") (pintype "input"))
      (node (ref "U16") (pin "6") (pinfunction "SDA/ADDR_6") (pintype "input"))
      (node (ref "U7") (pin "17") (pinfunction "SD6_17") (pintype "unspecified"))
    )
    (net (code "66") (name "SDA7") (class "Default")
      (node (ref "R20") (pin "1") (pinfunction "1_1") (pintype "input"))
      (node (ref "U17") (pin "6") (pinfunction "SDA/ADDR_6") (pintype "input"))
      (node (ref "U7") (pin "19") (pinfunction "SD7_19") (pintype "unspecified"))
    )
    (net (code "67") (name "UX_N_IN") (class "Default")
      (node (ref "CN1") (pin "9") (pinfunction "9_9") (pintype "unspecified"))
      (node (ref "U5") (pin "17") (pinfunction "17_17") (pintype "input"))
    )
    (net (code "68") (name "UX_N_OUT") (class "Default")
      (node (ref "CN1") (pin "1") (pinfunction "1_1") (pintype "unspecified"))
      (node (ref "U5") (pin "11") (pinfunction "11_11") (pintype "input"))
    )
    (net (code "69") (name "UX_P_IN") (class "Default")
      (node (ref "CN1") (pin "8") (pinfunction "8_8") (pintype "unspecified"))
      (node (ref "U5") (pin "16") (pinfunction "16_16") (pintype "input"))
    )
    (net (code "70") (name "UX_P_OUT") (class "Default")
      (node (ref "CN1") (pin "2") (pinfunction "2_2") (pintype "unspecified"))
      (node (ref "U5") (pin "10") (pinfunction "10_10") (pintype "input"))
    )
    (net (code "71") (name "UY_N_IN") (class "Default")
      (node (ref "CN1") (pin "3") (pinfunction "3_3") (pintype "unspecified"))
      (node (ref "U5") (pin "19") (pinfunction "19_19") (pintype "input"))
    )
    (net (code "72") (name "UY_N_OUT") (class "Default")
      (node (ref "CN1") (pin "7") (pinfunction "7_7") (pintype "unspecified"))
      (node (ref "U5") (pin "13") (pinfunction "13_13") (pintype "input"))
    )
    (net (code "73") (name "UY_P_IN") (class "Default")
      (node (ref "CN1") (pin "4") (pinfunction "4_4") (pintype "unspecified"))
      (node (ref "U5") (pin "18") (pinfunction "18_18") (pintype "input"))
    )
    (net (code "74") (name "UY_P_OUT") (class "Default")
      (node (ref "CN1") (pin "6") (pinfunction "6_6") (pintype "unspecified"))
      (node (ref "U5") (pin "12") (pinfunction "12_12") (pintype "input"))
    )
    (net (code "75") (name "VBUS") (class "Default")
      (node (ref "C1") (pin "1") (pinfunction "1_1") (pintype "input"))
      (node (ref "C15") (pin "1") (pinfunction "1_1") (pintype "input"))
      (node (ref "C16") (pin "1") (pinfunction "1_1") (pintype "input"))
      (node (ref "C17") (pin "1") (pinfunction "1_1") (pintype "input"))
      (node (ref "C18") (pin "1") (pinfunction "1_1") (pintype "input"))
      (node (ref "C19") (pin "1") (pinfunction "1_1") (pintype "input"))
      (node (ref "C20") (pin "1") (pinfunction "1_1") (pintype "input"))
      (node (ref "C21") (pin "1") (pinfunction "1_1") (pintype "input"))
      (node (ref "C22") (pin "1") (pinfunction "1_1") (pintype "input"))
      (node (ref "C3") (pin "1") (pinfunction "1_1") (pintype "input"))
      (node (ref "R27") (pin "2") (pinfunction "2_2") (pintype "input"))
      (node (ref "R29") (pin "2") (pinfunction "2_2") (pintype "input"))
      (node (ref "R5") (pin "2") (pinfunction "2_2") (pintype "input"))
      (node (ref "U1") (pin "3") (pinfunction "IN_3") (pintype "input"))
      (node (ref "U2") (pin "3") (pinfunction "IN_3") (pintype "input"))
      (node (ref "U20") (pin "5") (pinfunction "VBB_5") (pintype "unspecified"))
      (node (ref "U21") (pin "5") (pinfunction "VBB_5") (pintype "unspecified"))
      (node (ref "U22") (pin "5") (pinfunction "VBB_5") (pintype "unspecified"))
      (node (ref "U23") (pin "5") (pinfunction "VBB_5") (pintype "unspecified"))
      (node (ref "USBC1") (pin "A4") (pinfunction "VBUS_A4") (pintype "unspecified"))
      (node (ref "USBC1") (pin "A9") (pinfunction "VBUS_A9") (pintype "unspecified"))
      (node (ref "USBC1") (pin "B4") (pinfunction "VBUS_B4") (pintype "unspecified"))
      (node (ref "USBC1") (pin "B9") (pinfunction "VBUS_B9") (pintype "unspecified"))
    )
    (net (code "76") (name "unconnected-(U3-CFG2-Pad2)") (class "Default")
      (node (ref "U3") (pin "2") (pinfunction "CFG2_2") (pintype "unspecified+no_connect"))
    )
    (net (code "77") (name "unconnected-(U3-CFG3-Pad3)") (class "Default")
      (node (ref "U3") (pin "3") (pinfunction "CFG3_3") (pintype "unspecified+no_connect"))
    )
    (net (code "78") (name "unconnected-(U4-Pad2)") (class "Default")
      (node (ref "U4") (pin "2") (pinfunction "2_2") (pintype "input+no_connect"))
    )
    (net (code "79") (name "unconnected-(U4-Pad3)") (class "Default")
      (node (ref "U4") (pin "3") (pinfunction "3_3") (pintype "input+no_connect"))
    )
    (net (code "80") (name "unconnected-(U4-Pad12)") (class "Default")
      (node (ref "U4") (pin "12") (pinfunction "12_12") (pintype "input+no_connect"))
    )
    (net (code "81") (name "unconnected-(U4-Pad13)") (class "Default")
      (node (ref "U4") (pin "13") (pinfunction "13_13") (pintype "input+no_connect"))
    )
    (net (code "82") (name "unconnected-(U4-Pad14)") (class "Default")
      (node (ref "U4") (pin "14") (pinfunction "14_14") (pintype "input+no_connect"))
    )
    (net (code "83") (name "unconnected-(U4-Pad15)") (class "Default")
      (node (ref "U4") (pin "15") (pinfunction "15_15") (pintype "input+no_connect"))
    )
    (net (code "84") (name "unconnected-(U4-Pad19)") (class "Default")
      (node (ref "U4") (pin "19") (pinfunction "19_19") (pintype "input+no_connect"))
    )
    (net (code "85") (name "unconnected-(U4-Pad20)") (class "Default")
      (node (ref "U4") (pin "20") (pinfunction "20_20") (pintype "input+no_connect"))
    )
    (net (code "86") (name "unconnected-(U4-Pad21)") (class "Default")
      (node (ref "U4") (pin "21") (pinfunction "21_21") (pintype "input+no_connect"))
    )
    (net (code "87") (name "unconnected-(U4-Pad22)") (class "Default")
      (node (ref "U4") (pin "22") (pinfunction "22_22") (pintype "input+no_connect"))
    )
    (net (code "88") (name "unconnected-(U4-Pad23)") (class "Default")
      (node (ref "U4") (pin "23") (pinfunction "23_23") (pintype "input+no_connect"))
    )
    (net (code "89") (name "unconnected-(U4-Pad24)") (class "Default")
      (node (ref "U4") (pin "24") (pinfunction "24_24") (pintype "input+no_connect"))
    )
    (net (code "90") (name "unconnected-(U5-Pad3)") (class "Default")
      (node (ref "U5") (pin "3") (pinfunction "3_3") (pintype "input+no_connect"))
    )
    (net (code "91") (name "unconnected-(U5-Pad14)") (class "Default")
      (node (ref "U5") (pin "14") (pinfunction "14_14") (pintype "input+no_connect"))
    )
    (net (code "92") (name "unconnected-(U5-Pad20)") (class "Default")
      (node (ref "U5") (pin "20") (pinfunction "20_20") (pintype "input+no_connect"))
    )
    (net (code "93") (name "unconnected-(U5-Pad21)") (class "Default")
      (node (ref "U5") (pin "21") (pinfunction "21_21") (pintype "input+no_connect"))
    )
    (net (code "94") (name "unconnected-(U5-Pad22)") (class "Default")
      (node (ref "U5") (pin "22") (pinfunction "22_22") (pintype "input+no_connect"))
    )
    (net (code "95") (name "unconnected-(U5-Pad23)") (class "Default")
      (node (ref "U5") (pin "23") (pinfunction "23_23") (pintype "input+no_connect"))
    )
    (net (code "96") (name "unconnected-(U5-Pad24)") (class "Default")
      (node (ref "U5") (pin "24") (pinfunction "24_24") (pintype "input+no_connect"))
    )
    (net (code "97") (name "unconnected-(U40-2IN+-Pad5)") (class "Default")
      (node (ref "U40") (pin "5") (pinfunction "2IN+_5") (pintype "unspecified+no_connect"))
    )
    (net (code "98") (name "unconnected-(U40-2IN--Pad6)") (class "Default")
      (node (ref "U40") (pin "6") (pinfunction "2IN-_6") (pintype "unspecified+no_connect"))
    )
    (net (code "99") (name "unconnected-(U40-2OUT-Pad7)") (class "Default")
      (node (ref "U40") (pin "7") (pinfunction "2OUT_7") (pintype "unspecified+no_connect"))
    )
    (net (code "100") (name "unconnected-(USBC1-SBU1-PadA8)") (class "Default")
      (node (ref "USBC1") (pin "A8") (pinfunction "SBU1_A8") (pintype "unspecified+no_connect"))
    )
    (net (code "101") (name "unconnected-(USBC1-SBU2-PadB8)") (class "Default")
      (node (ref "USBC1") (pin "B8") (pinfunction "SBU2_B8") (pintype "unspecified+no_connect"))
    )
  )
)
